# shopbot2kflop.net
KiCad netlist of a schematic drawn in EAGLE
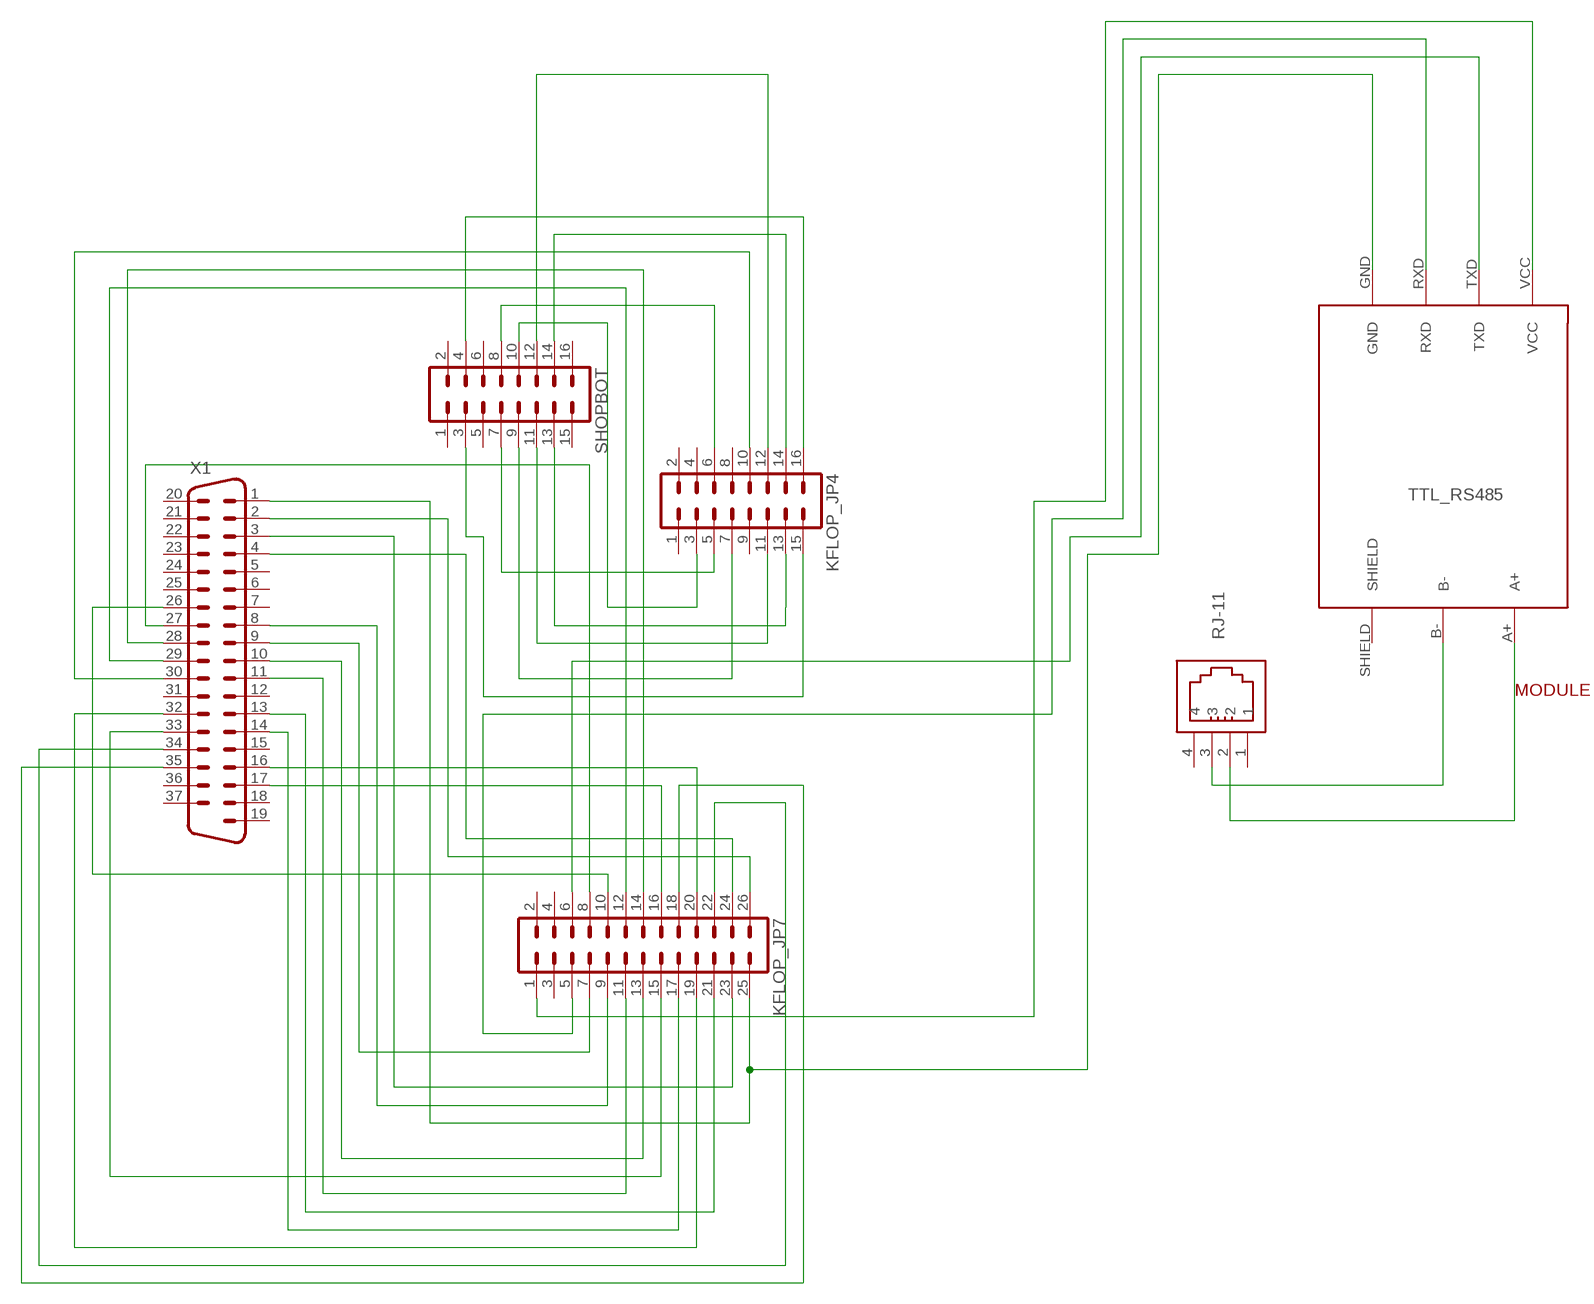
[diagram p0: schematic, sheet 1]

(export (version "E")
  (design (tool "Eeschema 10.0.6"))
  (components
    (comp (ref "KFLOP_JP4")
      (value "MA08-2")
      (footprint "eagle-import:MA08-2")
      (libsource (lib "eagle-import") (part "MA08-2"))
    )
    (comp (ref "KFLOP_JP7")
      (value "MA13-2")
      (footprint "eagle-import:MA13-2")
      (libsource (lib "eagle-import") (part "MA13-2"))
    )
    (comp (ref "MODULE")
      (value "TTL_RS485")
      (footprint "eagle-import:TTL_RS485")
      (libsource (lib "eagle-import") (part "TTL_RS485"))
    )
    (comp (ref "RJ-11")
      (value "615004144121")
      (footprint "eagle-import:615004144121")
      (libsource (lib "eagle-import") (part "615004144121"))
    )
    (comp (ref "SHOPBOT")
      (value "MA08-2")
      (footprint "eagle-import:MA08-2")
      (libsource (lib "eagle-import") (part "MA08-2"))
    )
    (comp (ref "X1")
      (value "M37HP")
      (footprint "eagle-import:M37HP")
      (libsource (lib "eagle-import") (part "M37HP"))
    )
  )
  (nets
    (net (code "1") (name "Net-(KFLOP_JP4-Pad3)") (class "Default")
      (node (ref "KFLOP_JP4") (pin "3") (pinfunction "3_3") (pintype "passive"))
      (node (ref "SHOPBOT") (pin "10") (pinfunction "10_10") (pintype "passive"))
    )
    (net (code "2") (name "Net-(KFLOP_JP4-Pad5)") (class "Default")
      (node (ref "KFLOP_JP4") (pin "5") (pinfunction "5_5") (pintype "passive"))
      (node (ref "SHOPBOT") (pin "7") (pinfunction "7_7") (pintype "passive"))
    )
    (net (code "3") (name "Net-(KFLOP_JP4-Pad6)") (class "Default")
      (node (ref "KFLOP_JP4") (pin "6") (pinfunction "6_6") (pintype "passive"))
      (node (ref "SHOPBOT") (pin "8") (pinfunction "8_8") (pintype "passive"))
    )
    (net (code "4") (name "Net-(KFLOP_JP4-Pad7)") (class "Default")
      (node (ref "KFLOP_JP4") (pin "7") (pinfunction "7_7") (pintype "passive"))
      (node (ref "SHOPBOT") (pin "9") (pinfunction "9_9") (pintype "passive"))
    )
    (net (code "5") (name "Net-(KFLOP_JP4-Pad10)") (class "Default")
      (node (ref "KFLOP_JP4") (pin "10") (pinfunction "10_10") (pintype "passive"))
      (node (ref "X1") (pin "30") (pinfunction "30_30") (pintype "passive"))
    )
    (net (code "6") (name "Net-(KFLOP_JP4-Pad11)") (class "Default")
      (node (ref "KFLOP_JP4") (pin "11") (pinfunction "11_11") (pintype "passive"))
      (node (ref "SHOPBOT") (pin "11") (pinfunction "11_11") (pintype "passive"))
    )
    (net (code "7") (name "Net-(KFLOP_JP4-Pad12)") (class "Default")
      (node (ref "KFLOP_JP4") (pin "12") (pinfunction "12_12") (pintype "passive"))
      (node (ref "SHOPBOT") (pin "12") (pinfunction "12_12") (pintype "passive"))
    )
    (net (code "8") (name "Net-(KFLOP_JP4-Pad13)") (class "Default")
      (node (ref "KFLOP_JP4") (pin "13") (pinfunction "13_13") (pintype "passive"))
      (node (ref "SHOPBOT") (pin "13") (pinfunction "13_13") (pintype "passive"))
    )
    (net (code "9") (name "Net-(KFLOP_JP4-Pad14)") (class "Default")
      (node (ref "KFLOP_JP4") (pin "14") (pinfunction "14_14") (pintype "passive"))
      (node (ref "SHOPBOT") (pin "14") (pinfunction "14_14") (pintype "passive"))
    )
    (net (code "10") (name "Net-(KFLOP_JP4-Pad15)") (class "Default")
      (node (ref "KFLOP_JP4") (pin "15") (pinfunction "15_15") (pintype "passive"))
      (node (ref "SHOPBOT") (pin "3") (pinfunction "3_3") (pintype "passive"))
    )
    (net (code "11") (name "Net-(KFLOP_JP4-Pad16)") (class "Default")
      (node (ref "KFLOP_JP4") (pin "16") (pinfunction "16_16") (pintype "passive"))
      (node (ref "SHOPBOT") (pin "4") (pinfunction "4_4") (pintype "passive"))
    )
    (net (code "12") (name "Net-(KFLOP_JP7-Pad1)") (class "Default")
      (node (ref "KFLOP_JP7") (pin "1") (pinfunction "1_1") (pintype "passive"))
      (node (ref "MODULE") (pin "VCC") (pinfunction "VCC_VCC") (pintype "bidirectional"))
    )
    (net (code "13") (name "Net-(KFLOP_JP7-Pad5)") (class "Default")
      (node (ref "KFLOP_JP7") (pin "5") (pinfunction "5_5") (pintype "passive"))
      (node (ref "MODULE") (pin "RXD") (pinfunction "RXD_RXD") (pintype "bidirectional"))
    )
    (net (code "14") (name "Net-(KFLOP_JP7-Pad6)") (class "Default")
      (node (ref "KFLOP_JP7") (pin "6") (pinfunction "6_6") (pintype "passive"))
      (node (ref "MODULE") (pin "TXD") (pinfunction "TXD_TXD") (pintype "bidirectional"))
    )
    (net (code "15") (name "Net-(KFLOP_JP7-Pad7)") (class "Default")
      (node (ref "KFLOP_JP7") (pin "7") (pinfunction "7_7") (pintype "passive"))
      (node (ref "X1") (pin "9") (pinfunction "9_9") (pintype "passive"))
    )
    (net (code "16") (name "Net-(KFLOP_JP7-Pad8)") (class "Default")
      (node (ref "KFLOP_JP7") (pin "8") (pinfunction "8_8") (pintype "passive"))
      (node (ref "X1") (pin "27") (pinfunction "27_27") (pintype "passive"))
    )
    (net (code "17") (name "Net-(KFLOP_JP7-Pad9)") (class "Default")
      (node (ref "KFLOP_JP7") (pin "9") (pinfunction "9_9") (pintype "passive"))
      (node (ref "X1") (pin "8") (pinfunction "8_8") (pintype "passive"))
    )
    (net (code "18") (name "Net-(KFLOP_JP7-Pad10)") (class "Default")
      (node (ref "KFLOP_JP7") (pin "10") (pinfunction "10_10") (pintype "passive"))
      (node (ref "X1") (pin "26") (pinfunction "26_26") (pintype "passive"))
    )
    (net (code "19") (name "Net-(KFLOP_JP7-Pad11)") (class "Default")
      (node (ref "KFLOP_JP7") (pin "11") (pinfunction "11_11") (pintype "passive"))
      (node (ref "X1") (pin "11") (pinfunction "11_11") (pintype "passive"))
    )
    (net (code "20") (name "Net-(KFLOP_JP7-Pad12)") (class "Default")
      (node (ref "KFLOP_JP7") (pin "12") (pinfunction "12_12") (pintype "passive"))
      (node (ref "X1") (pin "29") (pinfunction "29_29") (pintype "passive"))
    )
    (net (code "21") (name "Net-(KFLOP_JP7-Pad13)") (class "Default")
      (node (ref "KFLOP_JP7") (pin "13") (pinfunction "13_13") (pintype "passive"))
      (node (ref "X1") (pin "10") (pinfunction "10_10") (pintype "passive"))
    )
    (net (code "22") (name "Net-(KFLOP_JP7-Pad14)") (class "Default")
      (node (ref "KFLOP_JP7") (pin "14") (pinfunction "14_14") (pintype "passive"))
      (node (ref "X1") (pin "28") (pinfunction "28_28") (pintype "passive"))
    )
    (net (code "23") (name "Net-(KFLOP_JP7-Pad15)") (class "Default")
      (node (ref "KFLOP_JP7") (pin "15") (pinfunction "15_15") (pintype "passive"))
      (node (ref "X1") (pin "33") (pinfunction "33_33") (pintype "passive"))
    )
    (net (code "24") (name "Net-(KFLOP_JP7-Pad16)") (class "Default")
      (node (ref "KFLOP_JP7") (pin "16") (pinfunction "16_16") (pintype "passive"))
      (node (ref "X1") (pin "17") (pinfunction "17_17") (pintype "passive"))
    )
    (net (code "25") (name "Net-(KFLOP_JP7-Pad17)") (class "Default")
      (node (ref "KFLOP_JP7") (pin "17") (pinfunction "17_17") (pintype "passive"))
      (node (ref "X1") (pin "14") (pinfunction "14_14") (pintype "passive"))
    )
    (net (code "26") (name "Net-(KFLOP_JP7-Pad18)") (class "Default")
      (node (ref "KFLOP_JP7") (pin "18") (pinfunction "18_18") (pintype "passive"))
      (node (ref "X1") (pin "35") (pinfunction "35_35") (pintype "passive"))
    )
    (net (code "27") (name "Net-(KFLOP_JP7-Pad19)") (class "Default")
      (node (ref "KFLOP_JP7") (pin "19") (pinfunction "19_19") (pintype "passive"))
      (node (ref "X1") (pin "32") (pinfunction "32_32") (pintype "passive"))
    )
    (net (code "28") (name "Net-(KFLOP_JP7-Pad20)") (class "Default")
      (node (ref "KFLOP_JP7") (pin "20") (pinfunction "20_20") (pintype "passive"))
      (node (ref "X1") (pin "16") (pinfunction "16_16") (pintype "passive"))
    )
    (net (code "29") (name "Net-(KFLOP_JP7-Pad21)") (class "Default")
      (node (ref "KFLOP_JP7") (pin "21") (pinfunction "21_21") (pintype "passive"))
      (node (ref "X1") (pin "13") (pinfunction "13_13") (pintype "passive"))
    )
    (net (code "30") (name "Net-(KFLOP_JP7-Pad22)") (class "Default")
      (node (ref "KFLOP_JP7") (pin "22") (pinfunction "22_22") (pintype "passive"))
      (node (ref "X1") (pin "34") (pinfunction "34_34") (pintype "passive"))
    )
    (net (code "31") (name "Net-(KFLOP_JP7-Pad23)") (class "Default")
      (node (ref "KFLOP_JP7") (pin "23") (pinfunction "23_23") (pintype "passive"))
      (node (ref "X1") (pin "3") (pinfunction "3_3") (pintype "passive"))
    )
    (net (code "32") (name "Net-(KFLOP_JP7-Pad24)") (class "Default")
      (node (ref "KFLOP_JP7") (pin "24") (pinfunction "24_24") (pintype "passive"))
      (node (ref "X1") (pin "4") (pinfunction "4_4") (pintype "passive"))
    )
    (net (code "33") (name "Net-(KFLOP_JP7-Pad25)") (class "Default")
      (node (ref "KFLOP_JP7") (pin "25") (pinfunction "25_25") (pintype "passive"))
      (node (ref "MODULE") (pin "GND") (pinfunction "GND_GND") (pintype "bidirectional"))
      (node (ref "X1") (pin "1") (pinfunction "1_1") (pintype "passive"))
    )
    (net (code "34") (name "Net-(KFLOP_JP7-Pad26)") (class "Default")
      (node (ref "KFLOP_JP7") (pin "26") (pinfunction "26_26") (pintype "passive"))
      (node (ref "X1") (pin "2") (pinfunction "2_2") (pintype "passive"))
    )
    (net (code "35") (name "Net-(MODULE-PadA+)") (class "Default")
      (node (ref "MODULE") (pin "A+") (pinfunction "A+_A+") (pintype "bidirectional"))
      (node (ref "RJ-11") (pin "2") (pinfunction "2_2") (pintype "passive"))
    )
    (net (code "36") (name "Net-(MODULE-PadB-)") (class "Default")
      (node (ref "MODULE") (pin "B-") (pinfunction "B-_B-") (pintype "bidirectional"))
      (node (ref "RJ-11") (pin "3") (pinfunction "3_3") (pintype "passive"))
    )
    (net (code "37") (name "unconnected-(KFLOP_JP4-Pad1)") (class "Default")
      (node (ref "KFLOP_JP4") (pin "1") (pinfunction "1_1") (pintype "passive"))
    )
    (net (code "38") (name "unconnected-(KFLOP_JP4-Pad2)") (class "Default")
      (node (ref "KFLOP_JP4") (pin "2") (pinfunction "2_2") (pintype "passive"))
    )
    (net (code "39") (name "unconnected-(KFLOP_JP4-Pad4)") (class "Default")
      (node (ref "KFLOP_JP4") (pin "4") (pinfunction "4_4") (pintype "passive"))
    )
    (net (code "40") (name "unconnected-(KFLOP_JP4-Pad8)") (class "Default")
      (node (ref "KFLOP_JP4") (pin "8") (pinfunction "8_8") (pintype "passive"))
    )
    (net (code "41") (name "unconnected-(KFLOP_JP4-Pad9)") (class "Default")
      (node (ref "KFLOP_JP4") (pin "9") (pinfunction "9_9") (pintype "passive"))
    )
    (net (code "42") (name "unconnected-(KFLOP_JP7-Pad2)") (class "Default")
      (node (ref "KFLOP_JP7") (pin "2") (pinfunction "2_2") (pintype "passive"))
    )
    (net (code "43") (name "unconnected-(KFLOP_JP7-Pad3)") (class "Default")
      (node (ref "KFLOP_JP7") (pin "3") (pinfunction "3_3") (pintype "passive"))
    )
    (net (code "44") (name "unconnected-(KFLOP_JP7-Pad4)") (class "Default")
      (node (ref "KFLOP_JP7") (pin "4") (pinfunction "4_4") (pintype "passive"))
    )
    (net (code "45") (name "unconnected-(MODULE-PadSHIELD)") (class "Default")
      (node (ref "MODULE") (pin "SHIELD") (pinfunction "SHIELD_SHIELD") (pintype "bidirectional"))
    )
    (net (code "46") (name "unconnected-(RJ-11-Pad1)") (class "Default")
      (node (ref "RJ-11") (pin "1") (pinfunction "1_1") (pintype "passive"))
    )
    (net (code "47") (name "unconnected-(RJ-11-Pad4)") (class "Default")
      (node (ref "RJ-11") (pin "4") (pinfunction "4_4") (pintype "passive"))
    )
    (net (code "48") (name "unconnected-(SHOPBOT-Pad1)") (class "Default")
      (node (ref "SHOPBOT") (pin "1") (pinfunction "1_1") (pintype "passive"))
    )
    (net (code "49") (name "unconnected-(SHOPBOT-Pad2)") (class "Default")
      (node (ref "SHOPBOT") (pin "2") (pinfunction "2_2") (pintype "passive"))
    )
    (net (code "50") (name "unconnected-(SHOPBOT-Pad5)") (class "Default")
      (node (ref "SHOPBOT") (pin "5") (pinfunction "5_5") (pintype "passive"))
    )
    (net (code "51") (name "unconnected-(SHOPBOT-Pad6)") (class "Default")
      (node (ref "SHOPBOT") (pin "6") (pinfunction "6_6") (pintype "passive"))
    )
    (net (code "52") (name "unconnected-(SHOPBOT-Pad15)") (class "Default")
      (node (ref "SHOPBOT") (pin "15") (pinfunction "15_15") (pintype "passive"))
    )
    (net (code "53") (name "unconnected-(SHOPBOT-Pad16)") (class "Default")
      (node (ref "SHOPBOT") (pin "16") (pinfunction "16_16") (pintype "passive"))
    )
    (net (code "54") (name "unconnected-(X1-Pad5)") (class "Default")
      (node (ref "X1") (pin "5") (pinfunction "5_5") (pintype "passive"))
    )
    (net (code "55") (name "unconnected-(X1-Pad6)") (class "Default")
      (node (ref "X1") (pin "6") (pinfunction "6_6") (pintype "passive"))
    )
    (net (code "56") (name "unconnected-(X1-Pad7)") (class "Default")
      (node (ref "X1") (pin "7") (pinfunction "7_7") (pintype "passive"))
    )
    (net (code "57") (name "unconnected-(X1-Pad12)") (class "Default")
      (node (ref "X1") (pin "12") (pinfunction "12_12") (pintype "passive"))
    )
    (net (code "58") (name "unconnected-(X1-Pad15)") (class "Default")
      (node (ref "X1") (pin "15") (pinfunction "15_15") (pintype "passive"))
    )
    (net (code "59") (name "unconnected-(X1-Pad18)") (class "Default")
      (node (ref "X1") (pin "18") (pinfunction "18_18") (pintype "passive"))
    )
    (net (code "60") (name "unconnected-(X1-Pad19)") (class "Default")
      (node (ref "X1") (pin "19") (pinfunction "19_19") (pintype "passive"))
    )
    (net (code "61") (name "unconnected-(X1-Pad20)") (class "Default")
      (node (ref "X1") (pin "20") (pinfunction "20_20") (pintype "passive"))
    )
    (net (code "62") (name "unconnected-(X1-Pad21)") (class "Default")
      (node (ref "X1") (pin "21") (pinfunction "21_21") (pintype "passive"))
    )
    (net (code "63") (name "unconnected-(X1-Pad22)") (class "Default")
      (node (ref "X1") (pin "22") (pinfunction "22_22") (pintype "passive"))
    )
    (net (code "64") (name "unconnected-(X1-Pad23)") (class "Default")
      (node (ref "X1") (pin "23") (pinfunction "23_23") (pintype "passive"))
    )
    (net (code "65") (name "unconnected-(X1-Pad24)") (class "Default")
      (node (ref "X1") (pin "24") (pinfunction "24_24") (pintype "passive"))
    )
    (net (code "66") (name "unconnected-(X1-Pad25)") (class "Default")
      (node (ref "X1") (pin "25") (pinfunction "25_25") (pintype "passive"))
    )
    (net (code "67") (name "unconnected-(X1-Pad31)") (class "Default")
      (node (ref "X1") (pin "31") (pinfunction "31_31") (pintype "passive"))
    )
    (net (code "68") (name "unconnected-(X1-Pad36)") (class "Default")
      (node (ref "X1") (pin "36") (pinfunction "36_36") (pintype "passive"))
    )
    (net (code "69") (name "unconnected-(X1-Pad37)") (class "Default")
      (node (ref "X1") (pin "37") (pinfunction "37_37") (pintype "passive"))
    )
  )
)
